# PowerManagement.net
KiCad netlist of a schematic drawn in Altium Designer
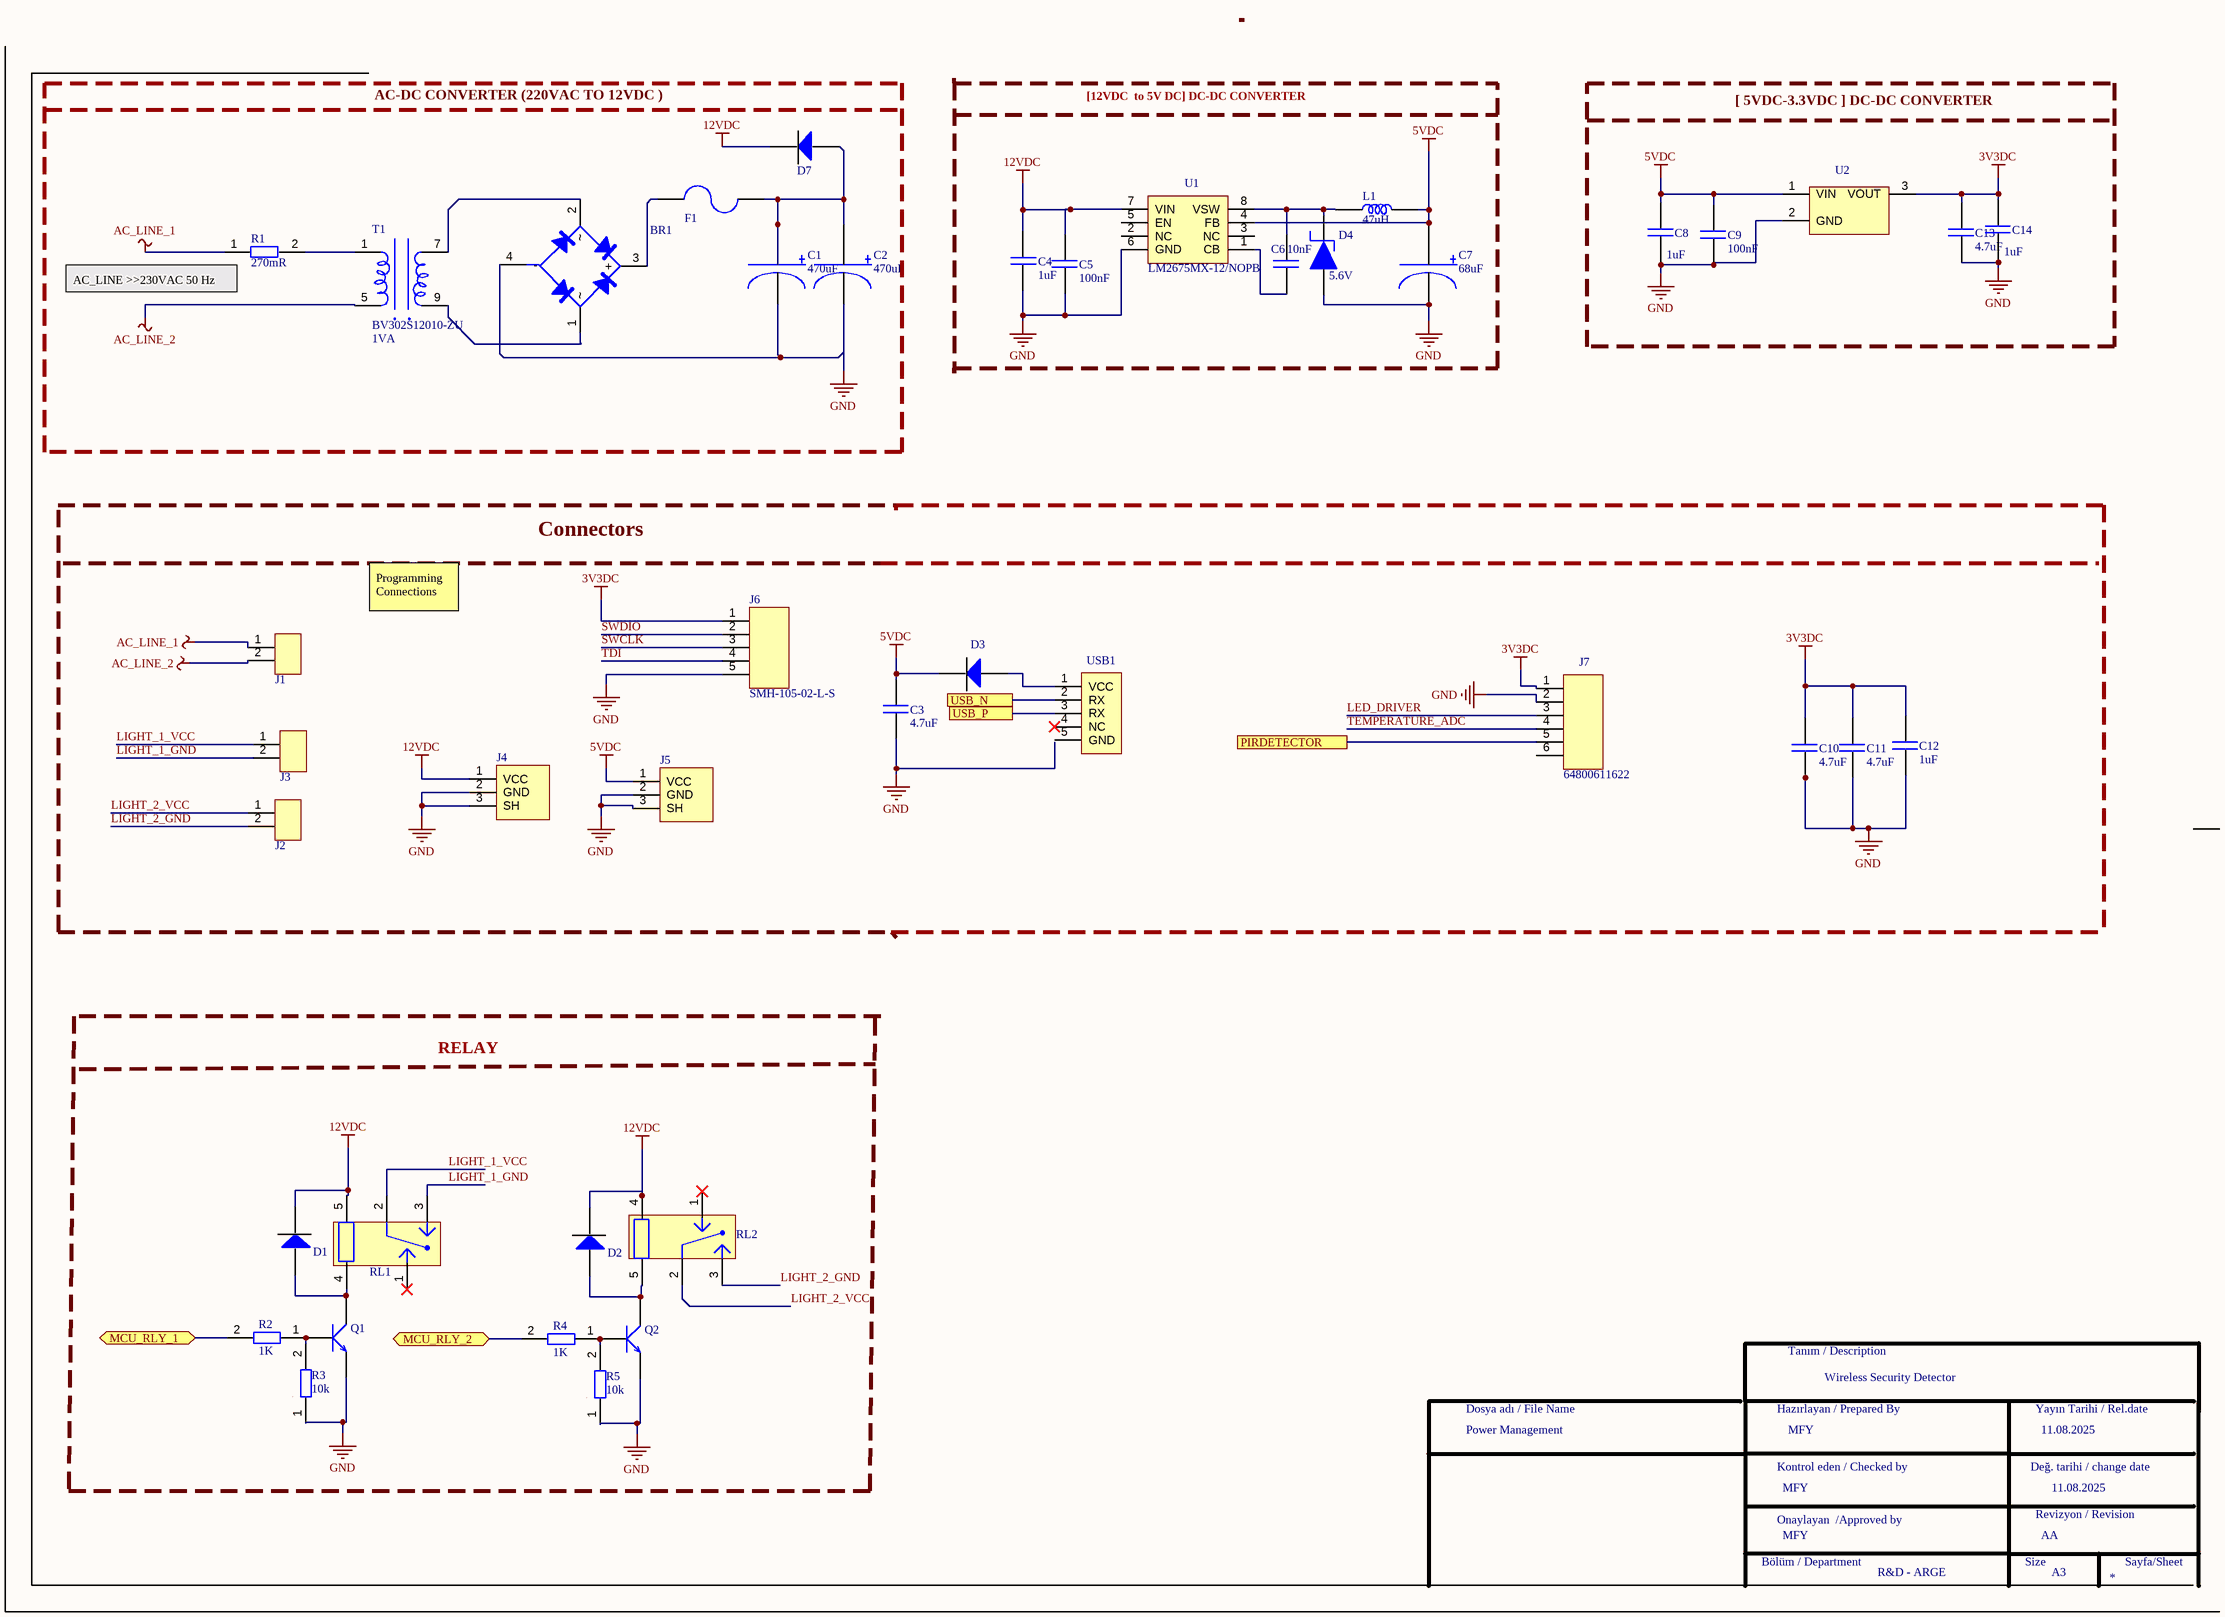
[diagram p0: PowerManagement.SchDoc]

(export (version "E")
  (design (tool "Eeschema 10.0.6"))
  (components
    (comp (ref "BR1")
      (value "DB105STR")
      (footprint "DB105STR")
      (description "Bridge Rect 1PHASE 600V 1A Db-s")
      (fields (field (name "MANUFACTURER") "SMC"))
      (libsource (lib "Udemy_Library") (part "DB105STR"))
    )
    (comp (ref "C1")
      (value "470uF")
      (footprint "CAP_RADIAL_D10_P5")
      (fields
        (field (name "MANUFACTURER") "KEMET")
        (field (name "MANUFACTURER PART NUMBER") "ESH477M050AH4AA")
      )
      (libsource (lib "Udemy_Library") (part "CAP ALU ELEC 470uF 50V"))
    )
    (comp (ref "C2")
      (value "470uF")
      (footprint "CAP_RADIAL_D10_P5")
      (fields
        (field (name "MANUFACTURER") "KEMET")
        (field (name "MANUFACTURER PART NUMBER") "ESH477M050AH4AA")
      )
      (libsource (lib "Udemy_Library") (part "CAP ALU ELEC 470uF 50V"))
    )
    (comp (ref "C3")
      (value "4.7uF")
      (footprint "CAP_0805")
      (fields
        (field (name "MANUFACTURER") "Samsung")
        (field (name "MANUFACTURER PART NUMBER") "CL21A475KAQNNNE")
      )
      (libsource (lib "Udemy_Library") (part "CAP CER 4.7uF 0805"))
    )
    (comp (ref "C4")
      (value "1uF")
      (footprint "CAP_0805")
      (fields
        (field (name "MANUFACTURER") "Samsung")
        (field (name "MANUFACTURER PART NUMBER") "CL21B105KBFNNNE")
      )
      (libsource (lib "Udemy_Library") (part "CAP CER 1uF 0805"))
    )
    (comp (ref "C5")
      (value "100nF")
      (footprint "CAP_0805")
      (fields
        (field (name "MANUFACTURER") "Samsung")
        (field (name "MANUFACTURER PART NUMBER") "CL21B104KBCNNNC")
      )
      (libsource (lib "Udemy_Library") (part "CAP CER 100nF 0805"))
    )
    (comp (ref "C6")
      (value "10nF")
      (footprint "CAP_0603")
      (fields
        (field (name "MANUFACTURER") "Walsin Technologies")
        (field (name "MANUFACTURER PART NUMBER") "0603B103K160CT")
      )
      (libsource (lib "Udemy_Library") (part "CAP CER 10nF 0603"))
    )
    (comp (ref "C7")
      (value "68uF")
      (footprint "CAP_EEVseries")
      (fields
        (field (name "MANUFACTURER") "KEMET")
        (field (name "MANUFACTURER PART NUMBER") "EEV686M035A9HAA")
      )
      (libsource (lib "Udemy_Library") (part "CAP ALU 68uF"))
    )
    (comp (ref "C8")
      (value "1uF")
      (footprint "CAP_0805")
      (fields
        (field (name "MANUFACTURER") "Samsung")
        (field (name "MANUFACTURER PART NUMBER") "CL21B105KBFNNNE")
      )
      (libsource (lib "Udemy_Library") (part "CAP CER 1uF 0805"))
    )
    (comp (ref "C9")
      (value "100nF")
      (footprint "CAP_0603")
      (description "CAP CER %10 100 nF 0603 Kemet")
      (fields
        (field (name "MANUFACTURER") "KEMET")
        (field (name "MANUFACTURER PART NUMBER") "C0603C104K5RACTU")
      )
      (libsource (lib "Udemy_Library") (part "CAP CER 100nF 0603"))
    )
    (comp (ref "C10")
      (value "4.7uF")
      (footprint "CAP_0805")
      (fields
        (field (name "MANUFACTURER") "Samsung")
        (field (name "MANUFACTURER PART NUMBER") "CL21A475KAQNNNE")
      )
      (libsource (lib "Udemy_Library") (part "CAP CER 4.7uF 0805"))
    )
    (comp (ref "C11")
      (value "4.7uF")
      (footprint "CAP_0805")
      (fields
        (field (name "MANUFACTURER") "Samsung")
        (field (name "MANUFACTURER PART NUMBER") "CL21A475KAQNNNE")
      )
      (libsource (lib "Udemy_Library") (part "CAP CER 4.7uF 0805"))
    )
    (comp (ref "C12")
      (value "1uF")
      (footprint "CAP_0805")
      (fields
        (field (name "MANUFACTURER") "Samsung")
        (field (name "MANUFACTURER PART NUMBER") "CL21B105KBFNNNE")
      )
      (libsource (lib "Udemy_Library") (part "CAP CER 1uF 0805"))
    )
    (comp (ref "C13")
      (value "4.7uF")
      (footprint "CAP_0805")
      (fields
        (field (name "MANUFACTURER") "Samsung")
        (field (name "MANUFACTURER PART NUMBER") "CL21A475KAQNNNE")
      )
      (libsource (lib "Udemy_Library") (part "CAP CER 4.7uF 0805"))
    )
    (comp (ref "C14")
      (value "1uF")
      (footprint "CAP_0805")
      (fields
        (field (name "MANUFACTURER") "Samsung")
        (field (name "MANUFACTURER PART NUMBER") "CL21B105KBFNNNE")
      )
      (libsource (lib "Udemy_Library") (part "CAP CER 1uF 0805"))
    )
    (comp (ref "D1")
      (value "1N4148WS")
      (footprint "SOD323F")
      (description "Rectifier Diode, 1 Phase, 1 Element, 0.15A, 100V V(RRM), Silicon")
      (fields (field (name "MANUFACTURER") "onsemi"))
      (libsource (lib "Udemy_Library") (part "1N4148WS"))
    )
    (comp (ref "D2")
      (value "1N4148WS")
      (footprint "SOD323F")
      (description "Rectifier Diode, 1 Phase, 1 Element, 0.15A, 100V V(RRM), Silicon")
      (fields (field (name "MANUFACTURER") "onsemi"))
      (libsource (lib "Udemy_Library") (part "1N4148WS"))
    )
    (comp (ref "D3")
      (value "1N4148WS")
      (footprint "SOD323F")
      (description "Rectifier Diode, 1 Phase, 1 Element, 0.15A, 100V V(RRM), Silicon")
      (fields (field (name "MANUFACTURER") "onsemi"))
      (libsource (lib "Udemy_Library") (part "1N4148WS"))
    )
    (comp (ref "D4")
      (value "1SMB5919BT3G")
      (footprint "SMB")
      (description "Zener Diode 5.6 V 3 W ±5% Surface Mount SMB")
      (fields (field (name "WORKING VOLTAGE") "5.6V"))
      (libsource (lib "Udemy_Library") (part "1SMB5919BT3G"))
    )
    (comp (ref "D7")
      (value "1N4148WS")
      (footprint "SOD323F")
      (description "Rectifier Diode, 1 Phase, 1 Element, 0.15A, 100V V(RRM), Silicon")
      (fields (field (name "MANUFACTURER") "onsemi"))
      (libsource (lib "Udemy_Library") (part "1N4148WS"))
    )
    (comp (ref "F1")
      (value "FUSE 3413.0216.22")
      (footprint "3413.0216.22")
      (description "Electric Fuse, Very Fast Blow, 1A, 32VAC, 63VDC, 63A (IR), Surface Mount, 1206")
      (fields
        (field (name "MANUFACTURER") "Schurter")
        (field (name "MANUFACTURER PART NUMBER") "3413.0216.22")
      )
      (libsource (lib "Udemy_Library") (part "FUSE 3413.0216.22"))
    )
    (comp (ref "J1")
      (value "TBP01R1-508-02BE")
      (footprint "TBP01R1-508")
      (description "Strip Terminal Block")
      (fields (field (name "MANUFACTURER") "Same Sky") (field (name "DESIGNED BY") "MFY"))
      (libsource (lib "Udemy_Library") (part "TBP01R1-508-02BE"))
    )
    (comp (ref "J2")
      (value "TBP01R1-508-02BE")
      (footprint "TBP01R1-508")
      (description "Strip Terminal Block")
      (fields (field (name "MANUFACTURER") "Same Sky") (field (name "DESIGNED BY") "MFY"))
      (libsource (lib "Udemy_Library") (part "TBP01R1-508-02BE"))
    )
    (comp (ref "J3")
      (value "TBP01R1-508-02BE")
      (footprint "TBP01R1-508")
      (description "Strip Terminal Block")
      (fields (field (name "MANUFACTURER") "Same Sky") (field (name "DESIGNED BY") "MFY"))
      (libsource (lib "Udemy_Library") (part "TBP01R1-508-02BE"))
    )
    (comp (ref "J4")
      (value "PJ-037AH-SMT-TR")
      (footprint "JACK")
      (fields (field (name "DESIGNED BY") "MFY"))
      (libsource (lib "Udemy_Library") (part "PJ-037AH-SMT-TR"))
    )
    (comp (ref "J5")
      (value "PJ-037AH-SMT-TR")
      (footprint "JACK")
      (fields (field (name "DESIGNED BY") "MFY"))
      (libsource (lib "Udemy_Library") (part "PJ-037AH-SMT-TR"))
    )
    (comp (ref "J6")
      (value "SMH-105-02-L-S")
      (footprint "PIN_Headers1x5RA")
      (fields (field (name "MANUFACTURER") "Samtec"))
      (libsource (lib "Udemy_Library") (part "SMH-105-02-L-S"))
    )
    (comp (ref "J7")
      (value "64800611622")
      (footprint "64800611622_WÜRTH_CONN")
      (description "WR-WTB Wire-to-Board Connectors 1.50 mm(ANA KARTTAN SENSOR KARTA)")
      (fields (field (name "MANUFACTURER") "Wurth Electronics"))
      (libsource (lib "Udemy_Library") (part "64800611622_CONN_6PIN"))
    )
    (comp (ref "L1")
      (value "47uH")
      (footprint "IND_1212")
      (description "General Purpose Inductor, 47uH, 20%, 1 Element, Iron Alloy-Core, SMD, 1212")
      (fields
        (field (name "MANUFACTURER") "Wurth Electronics")
        (field (name "MANUFACTURER PART NUMBER") "78438335470")
      )
      (libsource (lib "Udemy_Library") (part "IND 47uH"))
    )
    (comp (ref "Q1")
      (value "MMBT3904-7-F")
      (footprint "SOT23-F")
      (fields (field (name "MANUFACTURER") "Diodes Zetex") (field (name "DESIGNED BY") "MFY"))
      (libsource (lib "Udemy_Library") (part "MMBT3904-7-F"))
    )
    (comp (ref "Q2")
      (value "MMBT3904-7-F")
      (footprint "SOT23-F")
      (fields (field (name "MANUFACTURER") "Diodes Zetex") (field (name "DESIGNED BY") "MFY"))
      (libsource (lib "Udemy_Library") (part "MMBT3904-7-F"))
    )
    (comp (ref "R1")
      (value "270mR")
      (footprint "RES_AXIAL_W")
      (description "Fixed Resistor, Wire Wound, 5W, 0.27ohm, 200V, 5% +/-Tol, 300ppm/Cel, 8738")
      (fields
        (field (name "MANUFACTURER") "NTE Electronics")
        (field (name "MANUFACTURER PART NUMBER") "5WD27")
        (field (name "DESIGNED BY") "MFY")
      )
      (libsource (lib "Udemy_Library") (part "5WD27"))
    )
    (comp (ref "R2")
      (value "1K")
      (footprint "RES_0603")
      (fields (field (name "Comment") "RES 1K OHM 0603"))
      (libsource (lib "Udemy_Library") (part "RES 1K OHM 0603"))
    )
    (comp (ref "R3")
      (value "10k")
      (footprint "RES_0603")
      (description "RES 10K %1 OHM 0603 SMD")
      (fields
        (field (name "MANUFACTURER") "Yageo Group")
        (field (name "MANUFACTURER PART NUMBER") "RC0603FR-0710KL")
        (field (name "DESIGNED BY") "MFY")
      )
      (libsource (lib "Udemy_Library") (part "RES 10K OHM 0603"))
    )
    (comp (ref "R4")
      (value "1K")
      (footprint "RES_0603")
      (fields (field (name "Comment") "RES 1K OHM 0603"))
      (libsource (lib "Udemy_Library") (part "RES 1K OHM 0603"))
    )
    (comp (ref "R5")
      (value "10k")
      (footprint "RES_0603")
      (description "RES 10K %1 OHM 0603 SMD")
      (fields
        (field (name "MANUFACTURER") "Yageo Group")
        (field (name "MANUFACTURER PART NUMBER") "RC0603FR-0710KL")
        (field (name "DESIGNED BY") "MFY")
      )
      (libsource (lib "Udemy_Library") (part "RES 10K OHM 0603"))
    )
    (comp (ref "RL1")
      (value "ALQ112")
      (footprint "ALQ112")
      (description "General Purpose Relay SPDT (1 Form C) 12VDC Coil Through Hole")
      (fields (field (name "MANUFACTURER") "Panasonic"))
      (libsource (lib "") (part "ALQ112_1"))
    )
    (comp (ref "RL2")
      (value "ALQ112")
      (footprint "ALQ112")
      (description "General Purpose Relay SPDT (1 Form C) 12VDC Coil Through Hole")
      (fields (field (name "MANUFACTURER") "Panasonic"))
      (libsource (lib "Udemy_Library") (part "ALQ112"))
    )
    (comp (ref "T1")
      (value "BV302S12010-ZU")
      (footprint "BV302S")
      (description "Split Bobbin Power Transformer, 230-12V 1VA")
      (fields
        (field (name "MANUFACTURER") "Zettler Magnetics")
        (field (name "MANUFACTURER PART NUMBER") "BV302S12010")
        (field (name "RATED POWER") "1VA")
        (field (name "DESIGNED BY") "MFY")
      )
      (libsource (lib "Udemy_Library") (part "BV302S12010-ZU"))
    )
    (comp (ref "U1")
      (value "LM2675MX-12/NOPB")
      (footprint "SOIC8")
      (description "Switching Regulator, Voltage-mode, 2.2A, 275kHz Switching Freq-Max, DMOS, PDSO8")
      (fields (field (name "MANUFACTURER") "TI National Semiconductor") (field (name "DESIGNED BY") "MFY"))
      (libsource (lib "Udemy_Library") (part "LM2675MX-12/NOPB"))
    )
    (comp (ref "U2")
      (value "AP7361-33E-13")
      (footprint "SOT-223")
      (description "Fixed Positive LDO Regulator, 3.3V, 0.7V Dropout, CMOS, PSSO3,SOT-223")
      (fields (field (name "MANUFACTURER") "Diodes") (field (name "DESIGNED BY") "MFY"))
      (libsource (lib "Udemy_Library") (part "AP7361-33E-13"))
    )
    (comp (ref "USB1")
      (value "10118192-0001LF")
      (footprint "MICRO_B_USB")
      (description "CONN USB MICRO B RECPT SMT R/A")
      (fields (field (name "MANUFACTURER") "Amphenol ICC / FCI"))
      (libsource (lib "Udemy_Library") (part "Micro B USB Connector"))
    )
  )
  (nets
    (net (code "1") (name "/LED_DRIVER") (class "Default")
      (node (ref "J7") (pin "3") (pinfunction "RX_3") (pintype "power_in"))
    )
    (net (code "2") (name "/LIGHT_1_GND") (class "Default")
      (node (ref "J3") (pin "2") (pinfunction "2_2") (pintype "power_in"))
      (node (ref "RL1") (pin "3") (pinfunction "3_3") (pintype "passive"))
    )
    (net (code "3") (name "/LIGHT_1_VCC") (class "Default")
      (node (ref "J3") (pin "1") (pinfunction "1_1") (pintype "power_in"))
      (node (ref "RL1") (pin "2") (pinfunction "2_2") (pintype "passive"))
    )
    (net (code "4") (name "/LIGHT_2_GND") (class "Default")
      (node (ref "J2") (pin "2") (pinfunction "2_2") (pintype "power_in"))
      (node (ref "RL2") (pin "3") (pinfunction "3_3") (pintype "passive"))
    )
    (net (code "5") (name "/LIGHT_2_VCC") (class "Default")
      (node (ref "J2") (pin "1") (pinfunction "1_1") (pintype "power_in"))
      (node (ref "RL2") (pin "2") (pinfunction "2_2") (pintype "passive"))
    )
    (net (code "6") (name "/MCU_RLY_1") (class "Default")
      (node (ref "R2") (pin "2") (pinfunction "2_2") (pintype "passive"))
    )
    (net (code "7") (name "/MCU_RLY_2") (class "Default")
      (node (ref "R4") (pin "2") (pinfunction "2_2") (pintype "passive"))
    )
    (net (code "8") (name "/PIRDETECTOR") (class "Default")
      (node (ref "J7") (pin "5") (pinfunction "GND_5") (pintype "power_in"))
    )
    (net (code "9") (name "/SWCLK") (class "Default")
      (node (ref "J6") (pin "3") (pinfunction "3_3") (pintype "passive"))
    )
    (net (code "10") (name "/SWDIO") (class "Default")
      (node (ref "J6") (pin "2") (pinfunction "2_2") (pintype "passive"))
    )
    (net (code "11") (name "/TDI") (class "Default")
      (node (ref "J6") (pin "4") (pinfunction "4_4") (pintype "passive"))
    )
    (net (code "12") (name "/TEMPERATURE_ADC") (class "Default")
      (node (ref "J7") (pin "4") (pinfunction "NC_4") (pintype "power_in"))
    )
    (net (code "13") (name "/USB_N") (class "Default")
      (node (ref "USB1") (pin "2") (pinfunction "RX_2") (pintype "passive"))
    )
    (net (code "14") (name "/USB_P") (class "Default")
      (node (ref "USB1") (pin "3") (pinfunction "RX_3") (pintype "passive"))
    )
    (net (code "15") (name "3V3DC") (class "Default")
      (node (ref "C10") (pin "2") (pinfunction "2_2") (pintype "passive"))
      (node (ref "C11") (pin "2") (pinfunction "2_2") (pintype "passive"))
      (node (ref "C12") (pin "2") (pinfunction "2_2") (pintype "passive"))
      (node (ref "C13") (pin "2") (pinfunction "2_2") (pintype "passive"))
      (node (ref "C14") (pin "2") (pinfunction "2_2") (pintype "passive"))
      (node (ref "J6") (pin "1") (pinfunction "1_1") (pintype "passive"))
      (node (ref "J7") (pin "1") (pinfunction "VCC_1") (pintype "power_in"))
      (node (ref "U2") (pin "3") (pinfunction "VOUT_3") (pintype "passive"))
    )
    (net (code "16") (name "5VDC") (class "Default")
      (node (ref "C3") (pin "2") (pinfunction "2_2") (pintype "passive"))
      (node (ref "C7") (pin "1") (pinfunction "1_1") (pintype "passive"))
      (node (ref "C8") (pin "2") (pinfunction "2_2") (pintype "passive"))
      (node (ref "C9") (pin "2") (pinfunction "2_2") (pintype "passive"))
      (node (ref "D3") (pin "1") (pinfunction "1_1") (pintype "passive"))
      (node (ref "J5") (pin "1") (pinfunction "VCC_1") (pintype "passive"))
      (node (ref "L1") (pin "2") (pinfunction "2_2") (pintype "passive"))
      (node (ref "U1") (pin "4") (pinfunction "FB_4") (pintype "passive"))
      (node (ref "U2") (pin "1") (pinfunction "VIN_1") (pintype "passive"))
    )
    (net (code "17") (name "12VDC") (class "Default")
      (node (ref "C4") (pin "1") (pinfunction "1_1") (pintype "passive"))
      (node (ref "C5") (pin "2") (pinfunction "2_2") (pintype "passive"))
      (node (ref "D1") (pin "1") (pinfunction "1_1") (pintype "passive"))
      (node (ref "D2") (pin "1") (pinfunction "1_1") (pintype "passive"))
      (node (ref "D7") (pin "1") (pinfunction "1_1") (pintype "passive"))
      (node (ref "J4") (pin "1") (pinfunction "VCC_1") (pintype "passive"))
      (node (ref "RL1") (pin "5") (pinfunction "5_5") (pintype "passive"))
      (node (ref "RL2") (pin "4") (pinfunction "4_4") (pintype "passive"))
      (node (ref "U1") (pin "7") (pinfunction "VIN_7") (pintype "passive"))
    )
    (net (code "18") (name "AC_LINE_1") (class "Default")
      (node (ref "J1") (pin "1") (pinfunction "1_1") (pintype "power_in"))
      (node (ref "R1") (pin "1") (pinfunction "1_1") (pintype "passive"))
    )
    (net (code "19") (name "AC_LINE_2") (class "Default")
      (node (ref "J1") (pin "2") (pinfunction "2_2") (pintype "power_in"))
      (node (ref "T1") (pin "5") (pinfunction "5_5") (pintype "passive"))
    )
    (net (code "20") (name "GND") (class "Default")
      (node (ref "BR1") (pin "4") (pinfunction "-_4") (pintype "passive"))
      (node (ref "C1") (pin "2") (pinfunction "2_2") (pintype "passive"))
      (node (ref "C10") (pin "1") (pinfunction "1_1") (pintype "passive"))
      (node (ref "C11") (pin "1") (pinfunction "1_1") (pintype "passive"))
      (node (ref "C12") (pin "1") (pinfunction "1_1") (pintype "passive"))
      (node (ref "C13") (pin "1") (pinfunction "1_1") (pintype "passive"))
      (node (ref "C14") (pin "1") (pinfunction "1_1") (pintype "passive"))
      (node (ref "C2") (pin "2") (pinfunction "2_2") (pintype "passive"))
      (node (ref "C3") (pin "1") (pinfunction "1_1") (pintype "passive"))
      (node (ref "C4") (pin "2") (pinfunction "2_2") (pintype "passive"))
      (node (ref "C5") (pin "1") (pinfunction "1_1") (pintype "passive"))
      (node (ref "C7") (pin "2") (pinfunction "2_2") (pintype "passive"))
      (node (ref "C8") (pin "1") (pinfunction "1_1") (pintype "passive"))
      (node (ref "C9") (pin "1") (pinfunction "1_1") (pintype "passive"))
      (node (ref "D4") (pin "A") (pinfunction "A_A") (pintype "passive"))
      (node (ref "J4") (pin "2") (pinfunction "GND_2") (pintype "passive"))
      (node (ref "J4") (pin "3") (pinfunction "SH_3") (pintype "passive"))
      (node (ref "J5") (pin "2") (pinfunction "GND_2") (pintype "passive"))
      (node (ref "J5") (pin "3") (pinfunction "SH_3") (pintype "passive"))
      (node (ref "J6") (pin "5") (pinfunction "5_5") (pintype "passive"))
      (node (ref "J7") (pin "2") (pinfunction "RX_2") (pintype "power_in"))
      (node (ref "Q1") (pin "2") (pinfunction "E_2") (pintype "passive"))
      (node (ref "Q2") (pin "2") (pinfunction "E_2") (pintype "passive"))
      (node (ref "R3") (pin "1") (pinfunction "1_1") (pintype "passive"))
      (node (ref "R5") (pin "1") (pinfunction "1_1") (pintype "passive"))
      (node (ref "U1") (pin "6") (pinfunction "GND_6") (pintype "passive"))
      (node (ref "U2") (pin "2") (pinfunction "GND_2") (pintype "passive"))
    )
    (net (code "21") (name "Net-(BR1-+)") (class "Default")
      (node (ref "BR1") (pin "3") (pinfunction "+_3") (pintype "passive"))
      (node (ref "F1") (pin "1") (pinfunction "G_1") (pintype "passive"))
    )
    (net (code "22") (name "Net-(BR1-~-Pad1)") (class "Default")
      (node (ref "BR1") (pin "1") (pinfunction "~_1") (pintype "passive"))
      (node (ref "T1") (pin "9") (pinfunction "9_9") (pintype "passive"))
    )
    (net (code "23") (name "Net-(BR1-~-Pad2)") (class "Default")
      (node (ref "BR1") (pin "2") (pinfunction "~_2") (pintype "passive"))
      (node (ref "T1") (pin "7") (pinfunction "7_7") (pintype "passive"))
    )
    (net (code "24") (name "Net-(C1-Pad1)") (class "Default")
      (node (ref "C1") (pin "1") (pinfunction "1_1") (pintype "passive"))
      (node (ref "C2") (pin "1") (pinfunction "1_1") (pintype "passive"))
      (node (ref "D7") (pin "2") (pinfunction "2_2") (pintype "passive"))
      (node (ref "F1") (pin "2") (pinfunction "2_2") (pintype "passive"))
    )
    (net (code "25") (name "Net-(Q1-B)") (class "Default")
      (node (ref "Q1") (pin "1") (pinfunction "B_1") (pintype "passive"))
      (node (ref "R2") (pin "1") (pinfunction "1_1") (pintype "passive"))
      (node (ref "R3") (pin "2") (pinfunction "2_2") (pintype "passive"))
    )
    (net (code "26") (name "Net-(Q1-C)") (class "Default")
      (node (ref "D1") (pin "2") (pinfunction "2_2") (pintype "passive"))
      (node (ref "Q1") (pin "3") (pinfunction "C_3") (pintype "passive"))
      (node (ref "RL1") (pin "4") (pinfunction "4_4") (pintype "passive"))
    )
    (net (code "27") (name "Net-(Q2-B)") (class "Default")
      (node (ref "Q2") (pin "1") (pinfunction "B_1") (pintype "passive"))
      (node (ref "R4") (pin "1") (pinfunction "1_1") (pintype "passive"))
      (node (ref "R5") (pin "2") (pinfunction "2_2") (pintype "passive"))
    )
    (net (code "28") (name "Net-(Q2-C)") (class "Default")
      (node (ref "D2") (pin "2") (pinfunction "2_2") (pintype "passive"))
      (node (ref "Q2") (pin "3") (pinfunction "C_3") (pintype "passive"))
      (node (ref "RL2") (pin "5") (pinfunction "5_5") (pintype "passive"))
    )
    (net (code "29") (name "Net-(R1-Pad2)") (class "Default")
      (node (ref "R1") (pin "2") (pinfunction "2_2") (pintype "passive"))
      (node (ref "T1") (pin "1") (pinfunction "1_1") (pintype "passive"))
    )
    (net (code "30") (name "Net-(U1-CB)") (class "Default")
      (node (ref "C6") (pin "1") (pinfunction "1_1") (pintype "passive"))
      (node (ref "U1") (pin "1") (pinfunction "CB_1") (pintype "passive"))
    )
    (net (code "31") (name "Net-(U1-VSW)") (class "Default")
      (node (ref "C6") (pin "2") (pinfunction "2_2") (pintype "passive"))
      (node (ref "D4") (pin "C") (pinfunction "C_C") (pintype "passive"))
      (node (ref "L1") (pin "1") (pinfunction "1_1") (pintype "passive"))
      (node (ref "U1") (pin "8") (pinfunction "VSW_8") (pintype "passive"))
    )
    (net (code "32") (name "Net-(USB1-VCC)") (class "Default")
      (node (ref "D3") (pin "2") (pinfunction "2_2") (pintype "passive"))
      (node (ref "USB1") (pin "1") (pinfunction "VCC_1") (pintype "passive"))
    )
    (net (code "33") (name "unconnected-(J7-GND-Pad6)") (class "Default")
      (node (ref "J7") (pin "6") (pinfunction "GND_6") (pintype "power_in"))
    )
    (net (code "34") (name "unconnected-(RL1-Pad1)") (class "Default")
      (node (ref "RL1") (pin "1") (pinfunction "1_1") (pintype "passive+no_connect"))
    )
    (net (code "35") (name "unconnected-(RL2-Pad1)") (class "Default")
      (node (ref "RL2") (pin "1") (pinfunction "1_1") (pintype "passive+no_connect"))
    )
    (net (code "36") (name "unconnected-(U1-EN-Pad5)") (class "Default")
      (node (ref "U1") (pin "5") (pinfunction "EN_5") (pintype "passive"))
    )
    (net (code "37") (name "unconnected-(U1-NC-Pad2)") (class "Default")
      (node (ref "U1") (pin "2") (pinfunction "NC_2") (pintype "passive"))
    )
    (net (code "38") (name "unconnected-(U1-NC-Pad3)") (class "Default")
      (node (ref "U1") (pin "3") (pinfunction "NC_3") (pintype "passive"))
    )
    (net (code "39") (name "unconnected-(USB1-GND-Pad5)") (class "Default")
      (node (ref "USB1") (pin "5") (pinfunction "GND_5") (pintype "passive"))
    )
    (net (code "40") (name "unconnected-(USB1-NC-Pad4)") (class "Default")
      (node (ref "USB1") (pin "4") (pinfunction "NC_4") (pintype "passive+no_connect"))
    )
  )
)
